# ArduinoLED.net
KiCad netlist of a schematic drawn in EAGLE
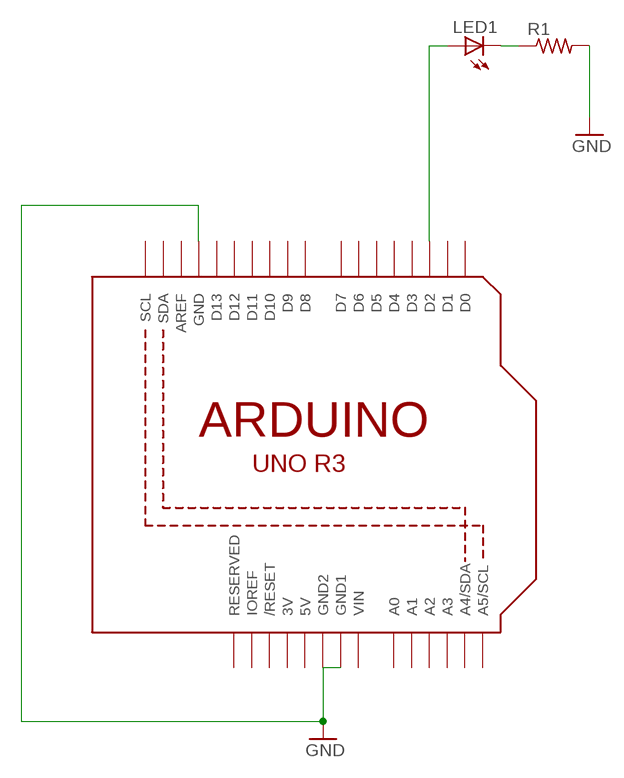
[diagram p0: schematic, sheet 1]

(export (version "E")
  (design (tool "Eeschema 10.0.6"))
  (components
    (comp (ref "LED1")
      (value "LED5MM")
      (footprint "eagle-import:LED5MM")
      (libsource (lib "eagle-import") (part "LED5MM"))
    )
    (comp (ref "R1")
      (value "R-US_0204/7")
      (footprint "eagle-import:0204_7")
      (libsource (lib "eagle-import") (part "R-US_0204/7"))
    )
    (comp (ref "U1")
      (value "ARDUINOR3-BPLACE")
      (footprint "eagle-import:ARDUINOR3-BPLACE")
      (libsource (lib "eagle-import") (part "ARDUINOR3-BPLACE"))
    )
  )
  (nets
    (net (code "1") (name "3V") (class "Default")
      (node (ref "U1") (pin "3V") (pinfunction "3V_3V") (pintype "power_in"))
    )
    (net (code "2") (name "5V") (class "Default")
      (node (ref "U1") (pin "5V") (pinfunction "5V_5V") (pintype "power_in"))
    )
    (net (code "3") (name "GND") (class "Default")
      (node (ref "R1") (pin "2") (pinfunction "2_2") (pintype "passive"))
      (node (ref "U1") (pin "GND") (pinfunction "GND_GND") (pintype "power_in"))
      (node (ref "U1") (pin "GND1") (pinfunction "GND1_GND1") (pintype "power_in"))
      (node (ref "U1") (pin "GND2") (pinfunction "GND2_GND2") (pintype "power_in"))
    )
    (net (code "4") (name "Net-(LED1-C)") (class "Default")
      (node (ref "LED1") (pin "K") (pinfunction "C_K") (pintype "passive"))
      (node (ref "R1") (pin "1") (pinfunction "1_1") (pintype "passive"))
    )
    (net (code "5") (name "Net-(LED1-PadA)") (class "Default")
      (node (ref "LED1") (pin "A") (pinfunction "A_A") (pintype "passive"))
      (node (ref "U1") (pin "D2") (pinfunction "D2_D2") (pintype "bidirectional"))
    )
    (net (code "6") (name "VIN") (class "Default")
      (node (ref "U1") (pin "VIN") (pinfunction "VIN_VIN") (pintype "power_in"))
    )
    (net (code "7") (name "unconnected-(U1-A4{slash}SDA-PadA4)") (class "Default")
      (node (ref "U1") (pin "A4") (pinfunction "A4/SDA_A4") (pintype "bidirectional"))
    )
    (net (code "8") (name "unconnected-(U1-A5{slash}SCL-PadA5)") (class "Default")
      (node (ref "U1") (pin "A5") (pinfunction "A5/SCL_A5") (pintype "bidirectional"))
    )
    (net (code "9") (name "unconnected-(U1-PadA0)") (class "Default")
      (node (ref "U1") (pin "A0") (pinfunction "A0_A0") (pintype "bidirectional"))
    )
    (net (code "10") (name "unconnected-(U1-PadA1)") (class "Default")
      (node (ref "U1") (pin "A1") (pinfunction "A1_A1") (pintype "bidirectional"))
    )
    (net (code "11") (name "unconnected-(U1-PadA2)") (class "Default")
      (node (ref "U1") (pin "A2") (pinfunction "A2_A2") (pintype "bidirectional"))
    )
    (net (code "12") (name "unconnected-(U1-PadA3)") (class "Default")
      (node (ref "U1") (pin "A3") (pinfunction "A3_A3") (pintype "bidirectional"))
    )
    (net (code "13") (name "unconnected-(U1-PadAREF)") (class "Default")
      (node (ref "U1") (pin "AREF") (pinfunction "AREF_AREF") (pintype "bidirectional"))
    )
    (net (code "14") (name "unconnected-(U1-PadD0)") (class "Default")
      (node (ref "U1") (pin "D0") (pinfunction "D0_D0") (pintype "bidirectional"))
    )
    (net (code "15") (name "unconnected-(U1-PadD1)") (class "Default")
      (node (ref "U1") (pin "D1") (pinfunction "D1_D1") (pintype "bidirectional"))
    )
    (net (code "16") (name "unconnected-(U1-PadD3)") (class "Default")
      (node (ref "U1") (pin "D3") (pinfunction "D3_D3") (pintype "bidirectional"))
    )
    (net (code "17") (name "unconnected-(U1-PadD4)") (class "Default")
      (node (ref "U1") (pin "D4") (pinfunction "D4_D4") (pintype "bidirectional"))
    )
    (net (code "18") (name "unconnected-(U1-PadD5)") (class "Default")
      (node (ref "U1") (pin "D5") (pinfunction "D5_D5") (pintype "bidirectional"))
    )
    (net (code "19") (name "unconnected-(U1-PadD6)") (class "Default")
      (node (ref "U1") (pin "D6") (pinfunction "D6_D6") (pintype "bidirectional"))
    )
    (net (code "20") (name "unconnected-(U1-PadD7)") (class "Default")
      (node (ref "U1") (pin "D7") (pinfunction "D7_D7") (pintype "bidirectional"))
    )
    (net (code "21") (name "unconnected-(U1-PadD8)") (class "Default")
      (node (ref "U1") (pin "D8") (pinfunction "D8_D8") (pintype "bidirectional"))
    )
    (net (code "22") (name "unconnected-(U1-PadD9)") (class "Default")
      (node (ref "U1") (pin "D9") (pinfunction "D9_D9") (pintype "bidirectional"))
    )
    (net (code "23") (name "unconnected-(U1-PadD10)") (class "Default")
      (node (ref "U1") (pin "D10") (pinfunction "D10_D10") (pintype "bidirectional"))
    )
    (net (code "24") (name "unconnected-(U1-PadD11)") (class "Default")
      (node (ref "U1") (pin "D11") (pinfunction "D11_D11") (pintype "bidirectional"))
    )
    (net (code "25") (name "unconnected-(U1-PadD12)") (class "Default")
      (node (ref "U1") (pin "D12") (pinfunction "D12_D12") (pintype "bidirectional"))
    )
    (net (code "26") (name "unconnected-(U1-PadD13)") (class "Default")
      (node (ref "U1") (pin "D13") (pinfunction "D13_D13") (pintype "bidirectional"))
    )
    (net (code "27") (name "unconnected-(U1-PadIOREF)") (class "Default")
      (node (ref "U1") (pin "IOREF") (pinfunction "IOREF_IOREF") (pintype "output"))
    )
    (net (code "28") (name "unconnected-(U1-PadRESERVED)") (class "Default")
      (node (ref "U1") (pin "RESERVED") (pinfunction "RESERVED_RESERVED") (pintype "no_connect"))
    )
    (net (code "29") (name "unconnected-(U1-PadSCL)") (class "Default")
      (node (ref "U1") (pin "SCL") (pinfunction "SCL_SCL") (pintype "bidirectional"))
    )
    (net (code "30") (name "unconnected-(U1-PadSDA)") (class "Default")
      (node (ref "U1") (pin "SDA") (pinfunction "SDA_SDA") (pintype "bidirectional"))
    )
    (net (code "31") (name "unconnected-(U1-{slash}RESET-PadRESET)") (class "Default")
      (node (ref "U1") (pin "RESET") (pinfunction "/RESET_RESET") (pintype "bidirectional"))
    )
  )
)
